# OSSI-1_Front_Panel.net
KiCad netlist of a schematic drawn in EAGLE
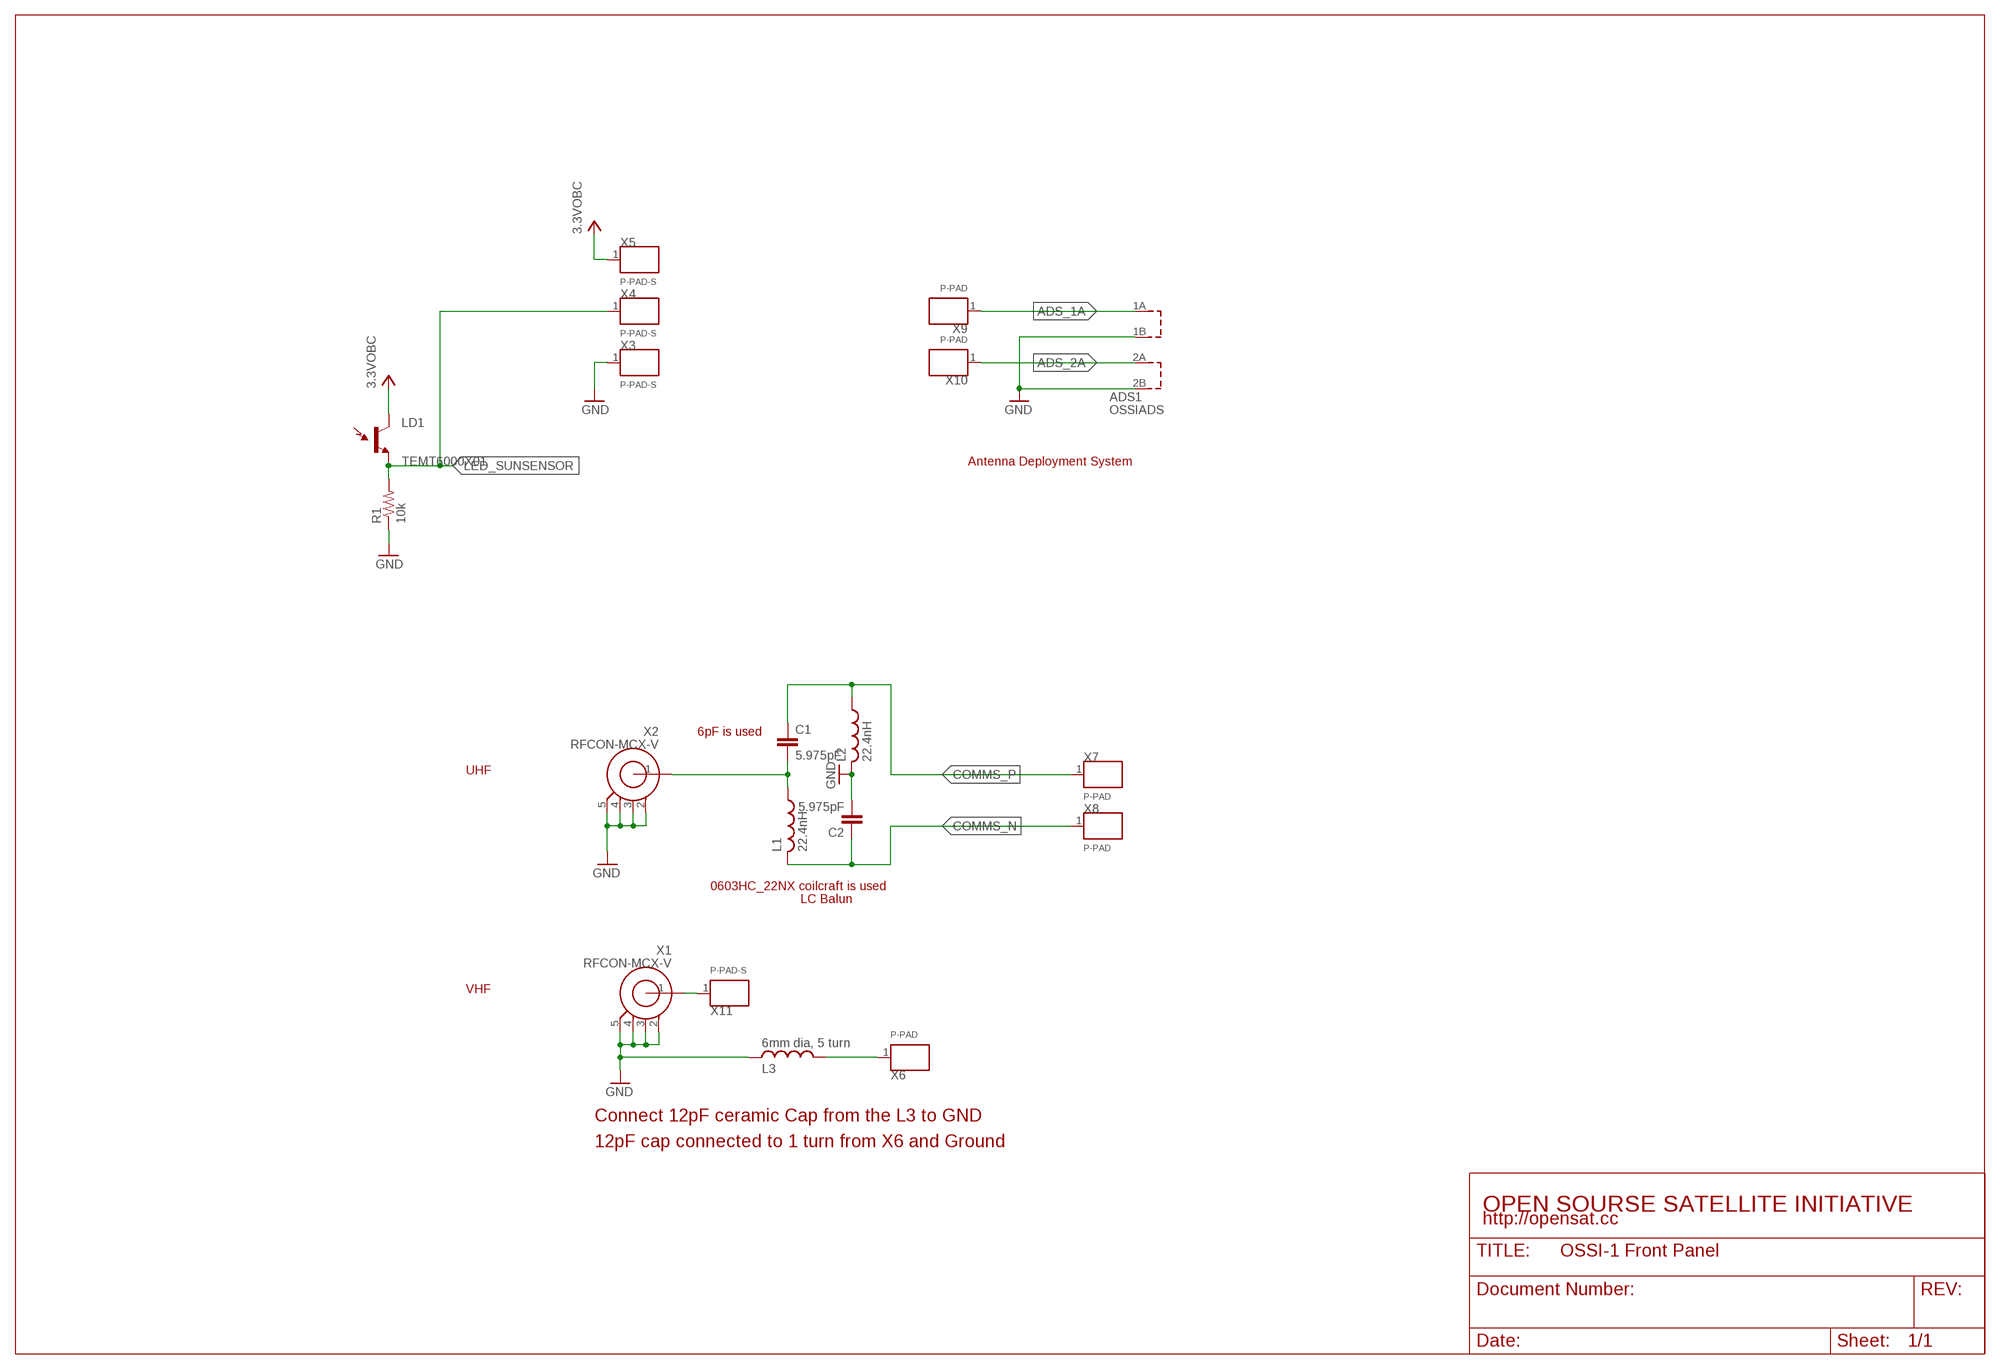
[diagram p0: schematic, sheet 1]

(export (version "E")
  (design (tool "Eeschema 10.0.6"))
  (components
    (comp (ref "ADS1")
      (value "OSSIADS")
      (footprint "eagle-import:OSSIADS")
      (libsource (lib "eagle-import") (part "OSSIADS"))
    )
    (comp (ref "C1")
      (value "5.975pF")
      (footprint "eagle-import:C0805(2012)")
      (libsource (lib "eagle-import") (part "C0805(2012)"))
    )
    (comp (ref "C2")
      (value "5.975pF")
      (footprint "eagle-import:C0805(2012)")
      (libsource (lib "eagle-import") (part "C0805(2012)"))
    )
    (comp (ref "L1")
      (value "22.4nH")
      (footprint "eagle-import:L0805(2012)")
      (libsource (lib "eagle-import") (part "L0805(2012)"))
    )
    (comp (ref "L2")
      (value "22.4nH")
      (footprint "eagle-import:L0805(2012)")
      (libsource (lib "eagle-import") (part "L0805(2012)"))
    )
    (comp (ref "L3")
      (value "6mm dia, 5 turn")
      (footprint "eagle-import:0207_10")
      (libsource (lib "eagle-import") (part "L-US0207/10"))
    )
    (comp (ref "LD1")
      (value "TEMT6000X01")
      (footprint "eagle-import:TEMT6000-SEN")
      (libsource (lib "eagle-import") (part "TEMT6000X01"))
    )
    (comp (ref "R1")
      (value "10k")
      (footprint "eagle-import:R0805(2012)")
      (libsource (lib "eagle-import") (part "R0805(2012)"))
    )
    (comp (ref "X1")
      (value "RFCON-MCX-V")
      (footprint "eagle-import:MCX-V")
      (libsource (lib "eagle-import") (part "RFCON-MCX-V"))
    )
    (comp (ref "X2")
      (value "RFCON-MCX-V")
      (footprint "eagle-import:MCX-V")
      (libsource (lib "eagle-import") (part "RFCON-MCX-V"))
    )
    (comp (ref "X3")
      (value "P-PAD-S")
      (footprint "eagle-import:P-PAD-S")
      (libsource (lib "eagle-import") (part "P-PAD-S"))
    )
    (comp (ref "X4")
      (value "P-PAD-S")
      (footprint "eagle-import:P-PAD-S")
      (libsource (lib "eagle-import") (part "P-PAD-S"))
    )
    (comp (ref "X5")
      (value "P-PAD-S")
      (footprint "eagle-import:P-PAD-S")
      (libsource (lib "eagle-import") (part "P-PAD-S"))
    )
    (comp (ref "X6")
      (value "P-PAD")
      (footprint "eagle-import:P-PAD")
      (libsource (lib "eagle-import") (part "P-PAD"))
    )
    (comp (ref "X7")
      (value "P-PAD")
      (footprint "eagle-import:P-PAD")
      (libsource (lib "eagle-import") (part "P-PAD"))
    )
    (comp (ref "X8")
      (value "P-PAD")
      (footprint "eagle-import:P-PAD")
      (libsource (lib "eagle-import") (part "P-PAD"))
    )
    (comp (ref "X9")
      (value "P-PAD")
      (footprint "eagle-import:P-PAD")
      (libsource (lib "eagle-import") (part "P-PAD"))
    )
    (comp (ref "X10")
      (value "P-PAD")
      (footprint "eagle-import:P-PAD")
      (libsource (lib "eagle-import") (part "P-PAD"))
    )
    (comp (ref "X11")
      (value "P-PAD-S")
      (footprint "eagle-import:P-PAD-S")
      (libsource (lib "eagle-import") (part "P-PAD-S"))
    )
  )
  (nets
    (net (code "1") (name "3.3VOBC") (class "Default")
      (node (ref "LD1") (pin "COLLECTOR") (pinfunction "C1_COLLECTOR") (pintype "passive"))
      (node (ref "X5") (pin "1") (pinfunction "P$1_1") (pintype "bidirectional"))
    )
    (net (code "2") (name "ADS_1A") (class "Default")
      (node (ref "ADS1") (pin "1A") (pinfunction "1A_1A") (pintype "passive"))
      (node (ref "X9") (pin "1") (pinfunction "P$1_1") (pintype "bidirectional"))
    )
    (net (code "3") (name "ADS_2A") (class "Default")
      (node (ref "ADS1") (pin "2A") (pinfunction "2A_2A") (pintype "passive"))
      (node (ref "X10") (pin "1") (pinfunction "P$1_1") (pintype "bidirectional"))
    )
    (net (code "4") (name "COMMS_N") (class "Default")
      (node (ref "C2") (pin "1") (pinfunction "1_1") (pintype "passive"))
      (node (ref "L1") (pin "2") (pinfunction "2_2") (pintype "passive"))
      (node (ref "X8") (pin "1") (pinfunction "P$1_1") (pintype "bidirectional"))
    )
    (net (code "5") (name "COMMS_P") (class "Default")
      (node (ref "C1") (pin "1") (pinfunction "1_1") (pintype "passive"))
      (node (ref "L2") (pin "1") (pinfunction "1_1") (pintype "passive"))
      (node (ref "X7") (pin "1") (pinfunction "P$1_1") (pintype "bidirectional"))
    )
    (net (code "6") (name "GND") (class "Default")
      (node (ref "ADS1") (pin "1B") (pinfunction "1B_1B") (pintype "passive"))
      (node (ref "ADS1") (pin "2B") (pinfunction "2B_2B") (pintype "passive"))
      (node (ref "C2") (pin "2") (pinfunction "2_2") (pintype "passive"))
      (node (ref "L2") (pin "2") (pinfunction "2_2") (pintype "passive"))
      (node (ref "L3") (pin "2") (pinfunction "2_2") (pintype "passive"))
      (node (ref "R1") (pin "1") (pinfunction "1_1") (pintype "passive"))
      (node (ref "X1") (pin "2") (pinfunction "2_2") (pintype "power_in"))
      (node (ref "X1") (pin "3") (pinfunction "3_3") (pintype "power_in"))
      (node (ref "X1") (pin "4") (pinfunction "4_4") (pintype "power_in"))
      (node (ref "X1") (pin "5") (pinfunction "5_5") (pintype "power_in"))
      (node (ref "X2") (pin "2") (pinfunction "2_2") (pintype "power_in"))
      (node (ref "X2") (pin "3") (pinfunction "3_3") (pintype "power_in"))
      (node (ref "X2") (pin "4") (pinfunction "4_4") (pintype "power_in"))
      (node (ref "X2") (pin "5") (pinfunction "5_5") (pintype "power_in"))
      (node (ref "X3") (pin "1") (pinfunction "P$1_1") (pintype "bidirectional"))
    )
    (net (code "7") (name "LED_SUNSENSOR") (class "Default")
      (node (ref "LD1") (pin "EMITTER") (pinfunction "E1_EMITTER") (pintype "passive"))
      (node (ref "R1") (pin "2") (pinfunction "2_2") (pintype "passive"))
      (node (ref "X4") (pin "1") (pinfunction "P$1_1") (pintype "bidirectional"))
    )
    (net (code "8") (name "Net-(C1-Pad2)") (class "Default")
      (node (ref "C1") (pin "2") (pinfunction "2_2") (pintype "passive"))
      (node (ref "L1") (pin "1") (pinfunction "1_1") (pintype "passive"))
      (node (ref "X2") (pin "1") (pinfunction "1_1") (pintype "bidirectional"))
    )
    (net (code "9") (name "Net-(X6-P$1)") (class "Default")
      (node (ref "L3") (pin "1") (pinfunction "1_1") (pintype "passive"))
      (node (ref "X6") (pin "1") (pinfunction "P$1_1") (pintype "bidirectional"))
    )
    (net (code "10") (name "Net-(X11-P$1)") (class "Default")
      (node (ref "X1") (pin "1") (pinfunction "1_1") (pintype "bidirectional"))
      (node (ref "X11") (pin "1") (pinfunction "P$1_1") (pintype "bidirectional"))
    )
  )
)
